# dwm1000v2.net
KiCad netlist of a schematic drawn in EAGLE
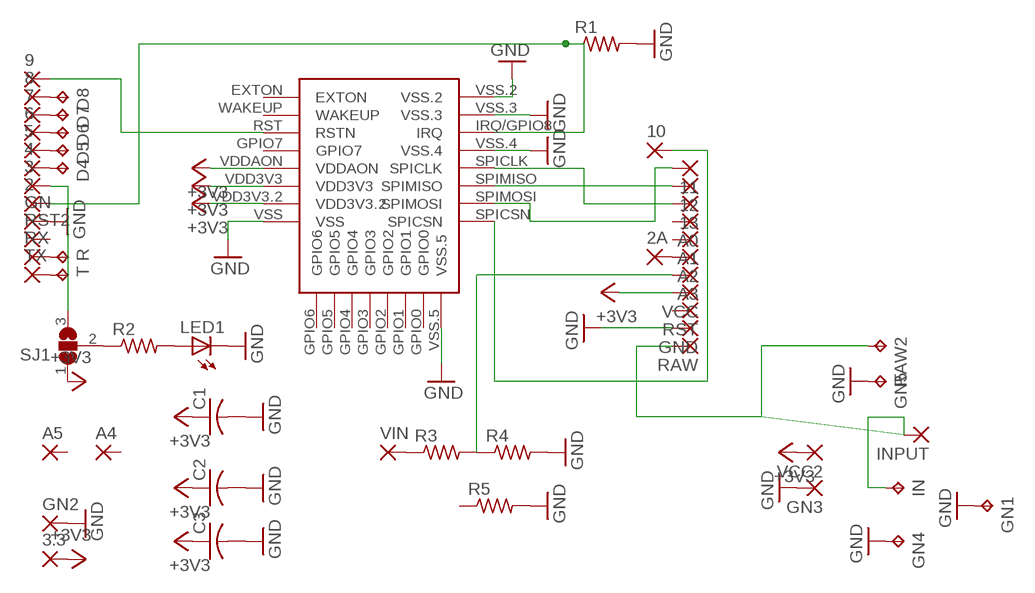
[diagram p0: schematic, sheet 1]

(export (version "E")
  (design (tool "Eeschema 10.0.6"))
  (components
    (comp (ref "2")
      (value "SMD2")
      (footprint "eagle-import:SMD1,27-2,54")
      (libsource (lib "eagle-import") (part "SMD2"))
    )
    (comp (ref "2A")
      (value "SMD2")
      (footprint "eagle-import:SMD1,27-2,54")
      (libsource (lib "eagle-import") (part "SMD2"))
    )
    (comp (ref "3")
      (value "SMD2")
      (footprint "eagle-import:SMD1,27-2,54")
      (libsource (lib "eagle-import") (part "SMD2"))
    )
    (comp (ref "3.3")
      (value "SMD2")
      (footprint "eagle-import:SMD1,27-2,54")
      (libsource (lib "eagle-import") (part "SMD2"))
    )
    (comp (ref "4")
      (value "SMD2")
      (footprint "eagle-import:SMD1,27-2,54")
      (libsource (lib "eagle-import") (part "SMD2"))
    )
    (comp (ref "5")
      (value "SMD2")
      (footprint "eagle-import:SMD1,27-2,54")
      (libsource (lib "eagle-import") (part "SMD2"))
    )
    (comp (ref "6")
      (value "SMD2")
      (footprint "eagle-import:SMD1,27-2,54")
      (libsource (lib "eagle-import") (part "SMD2"))
    )
    (comp (ref "7")
      (value "SMD2")
      (footprint "eagle-import:SMD1,27-2,54")
      (libsource (lib "eagle-import") (part "SMD2"))
    )
    (comp (ref "8")
      (value "SMD2")
      (footprint "eagle-import:SMD1,27-2,54")
      (libsource (lib "eagle-import") (part "SMD2"))
    )
    (comp (ref "9")
      (value "SMD2")
      (footprint "eagle-import:SMD1,27-2,54")
      (libsource (lib "eagle-import") (part "SMD2"))
    )
    (comp (ref "10")
      (value "SMD2")
      (footprint "eagle-import:SMD1,27-2,54")
      (libsource (lib "eagle-import") (part "SMD2"))
    )
    (comp (ref "11")
      (value "SMD2")
      (footprint "eagle-import:SMD1,27-2,54")
      (libsource (lib "eagle-import") (part "SMD2"))
    )
    (comp (ref "12")
      (value "SMD2")
      (footprint "eagle-import:SMD1,27-2,54")
      (libsource (lib "eagle-import") (part "SMD2"))
    )
    (comp (ref "13")
      (value "SMD2")
      (footprint "eagle-import:SMD1,27-2,54")
      (libsource (lib "eagle-import") (part "SMD2"))
    )
    (comp (ref "A0")
      (value "SMD2")
      (footprint "eagle-import:SMD1,27-2,54")
      (libsource (lib "eagle-import") (part "SMD2"))
    )
    (comp (ref "A1")
      (value "SMD2")
      (footprint "eagle-import:SMD1,27-2,54")
      (libsource (lib "eagle-import") (part "SMD2"))
    )
    (comp (ref "A2")
      (value "SMD2")
      (footprint "eagle-import:SMD1,27-2,54")
      (libsource (lib "eagle-import") (part "SMD2"))
    )
    (comp (ref "A3")
      (value "SMD2")
      (footprint "eagle-import:SMD1,27-2,54")
      (libsource (lib "eagle-import") (part "SMD2"))
    )
    (comp (ref "A4")
      (value "1,6/0,8")
      (footprint "eagle-import:1,6_0,8")
      (libsource (lib "eagle-import") (part "1,6/0,8"))
    )
    (comp (ref "A5")
      (value "1,6/0,8")
      (footprint "eagle-import:1,6_0,8")
      (libsource (lib "eagle-import") (part "1,6/0,8"))
    )
    (comp (ref "C1")
      (value "C-USC0805")
      (footprint "eagle-import:C0805")
      (libsource (lib "eagle-import") (part "C-USC0805"))
    )
    (comp (ref "C2")
      (value "C-USC0805")
      (footprint "eagle-import:C0805")
      (libsource (lib "eagle-import") (part "C-USC0805"))
    )
    (comp (ref "C3")
      (value "C-USC0805")
      (footprint "eagle-import:C0805")
      (libsource (lib "eagle-import") (part "C-USC0805"))
    )
    (comp (ref "D4")
      (value "TPTP12SQ")
      (footprint "eagle-import:TP12SQ")
      (libsource (lib "eagle-import") (part "TPTP12SQ"))
    )
    (comp (ref "D5")
      (value "TPTP12SQ")
      (footprint "eagle-import:TP12SQ")
      (libsource (lib "eagle-import") (part "TPTP12SQ"))
    )
    (comp (ref "D6")
      (value "TPTP12SQ")
      (footprint "eagle-import:TP12SQ")
      (libsource (lib "eagle-import") (part "TPTP12SQ"))
    )
    (comp (ref "D7")
      (value "TPTP12SQ")
      (footprint "eagle-import:TP12SQ")
      (libsource (lib "eagle-import") (part "TPTP12SQ"))
    )
    (comp (ref "D8")
      (value "TPTP12SQ")
      (footprint "eagle-import:TP12SQ")
      (libsource (lib "eagle-import") (part "TPTP12SQ"))
    )
    (comp (ref "GN")
      (value "SMD2")
      (footprint "eagle-import:SMD1,27-2,54")
      (libsource (lib "eagle-import") (part "SMD2"))
    )
    (comp (ref "GN1")
      (value "TPTP13SQ")
      (footprint "eagle-import:TP13SQ")
      (libsource (lib "eagle-import") (part "TPTP13SQ"))
    )
    (comp (ref "GN2")
      (value "SMD2")
      (footprint "eagle-import:SMD1,27-2,54")
      (libsource (lib "eagle-import") (part "SMD2"))
    )
    (comp (ref "GN3")
      (value "SMD2")
      (footprint "eagle-import:SMD1,27-2,54")
      (libsource (lib "eagle-import") (part "SMD2"))
    )
    (comp (ref "GN4")
      (value "TPTP13SQ")
      (footprint "eagle-import:TP13SQ")
      (libsource (lib "eagle-import") (part "TPTP13SQ"))
    )
    (comp (ref "GN5")
      (value "TPTP13SQ")
      (footprint "eagle-import:TP13SQ")
      (libsource (lib "eagle-import") (part "TPTP13SQ"))
    )
    (comp (ref "GND")
      (value "SMD2")
      (footprint "eagle-import:SMD1,27-2,54")
      (libsource (lib "eagle-import") (part "SMD2"))
    )
    (comp (ref "IN")
      (value "TPTP13SQ")
      (footprint "eagle-import:TP13SQ")
      (libsource (lib "eagle-import") (part "TPTP13SQ"))
    )
    (comp (ref "INPUT")
      (value "SMD2")
      (footprint "eagle-import:SMD1,27-2,54")
      (libsource (lib "eagle-import") (part "SMD2"))
    )
    (comp (ref "LED1")
      (value "LEDCHIPLED_0805")
      (footprint "eagle-import:CHIPLED_0805")
      (libsource (lib "eagle-import") (part "LEDCHIPLED_0805"))
    )
    (comp (ref "R")
      (value "TPTP12SQ")
      (footprint "eagle-import:TP12SQ")
      (libsource (lib "eagle-import") (part "TPTP12SQ"))
    )
    (comp (ref "R1")
      (value "R-US_R0603")
      (footprint "eagle-import:R0603")
      (libsource (lib "eagle-import") (part "R-US_R0603"))
    )
    (comp (ref "R2")
      (value "R-US_M0805")
      (footprint "eagle-import:M0805")
      (libsource (lib "eagle-import") (part "R-US_M0805"))
    )
    (comp (ref "R3")
      (value "R-US_R0805")
      (footprint "eagle-import:R0805")
      (libsource (lib "eagle-import") (part "R-US_R0805"))
    )
    (comp (ref "R4")
      (value "R-US_R0805")
      (footprint "eagle-import:R0805")
      (libsource (lib "eagle-import") (part "R-US_R0805"))
    )
    (comp (ref "R5")
      (value "R-US_R0805")
      (footprint "eagle-import:R0805")
      (libsource (lib "eagle-import") (part "R-US_R0805"))
    )
    (comp (ref "RAW")
      (value "SMD2")
      (footprint "eagle-import:SMD1,27-2,54")
      (libsource (lib "eagle-import") (part "SMD2"))
    )
    (comp (ref "RAW2")
      (value "TPTP13SQ")
      (footprint "eagle-import:TP13SQ")
      (libsource (lib "eagle-import") (part "TPTP13SQ"))
    )
    (comp (ref "RST")
      (value "SMD2")
      (footprint "eagle-import:SMD1,27-2,54")
      (libsource (lib "eagle-import") (part "SMD2"))
    )
    (comp (ref "RST2")
      (value "SMD2")
      (footprint "eagle-import:SMD1,27-2,54")
      (libsource (lib "eagle-import") (part "SMD2"))
    )
    (comp (ref "RX")
      (value "SMD2")
      (footprint "eagle-import:SMD1,27-2,54")
      (libsource (lib "eagle-import") (part "SMD2"))
    )
    (comp (ref "SJ1")
      (value "SJ2W")
      (footprint "eagle-import:SJ_2")
      (libsource (lib "eagle-import") (part "SJ2W"))
    )
    (comp (ref "T")
      (value "TPTP12SQ")
      (footprint "eagle-import:TP12SQ")
      (libsource (lib "eagle-import") (part "TPTP12SQ"))
    )
    (comp (ref "TX")
      (value "SMD2")
      (footprint "eagle-import:SMD1,27-2,54")
      (libsource (lib "eagle-import") (part "SMD2"))
    )
    (comp (ref "U$1")
      (value "DWM1000")
      (footprint "eagle-import:DWM1000")
      (libsource (lib "eagle-import") (part "DWM1000"))
    )
    (comp (ref "VCC")
      (value "SMD2")
      (footprint "eagle-import:SMD1,27-2,54")
      (libsource (lib "eagle-import") (part "SMD2"))
    )
    (comp (ref "VCC2")
      (value "SMD2")
      (footprint "eagle-import:SMD1,27-2,54")
      (libsource (lib "eagle-import") (part "SMD2"))
    )
    (comp (ref "VIN")
      (value "SMD2")
      (footprint "eagle-import:SMD1,27-2,54")
      (libsource (lib "eagle-import") (part "SMD2"))
    )
  )
  (nets
    (net (code "1") (name "+3V3") (class "Default")
      (node (ref "3.3") (pin "1") (pinfunction "P_1") (pintype "passive"))
      (node (ref "C1") (pin "1") (pinfunction "1_1") (pintype "passive"))
      (node (ref "C2") (pin "1") (pinfunction "1_1") (pintype "passive"))
      (node (ref "C3") (pin "1") (pinfunction "1_1") (pintype "passive"))
      (node (ref "SJ1") (pin "1") (pinfunction "1_1") (pintype "passive"))
      (node (ref "U$1") (pin "VDD3V3") (pinfunction "VDD3V3_VDD3V3") (pintype "bidirectional"))
      (node (ref "U$1") (pin "VDD3V3.2") (pinfunction "VDD3V3.2_VDD3V3.2") (pintype "bidirectional"))
      (node (ref "U$1") (pin "VDDAON") (pinfunction "VDDAON_VDDAON") (pintype "bidirectional"))
      (node (ref "VCC") (pin "1") (pinfunction "P_1") (pintype "passive"))
      (node (ref "VCC2") (pin "1") (pinfunction "P_1") (pintype "passive"))
    )
    (net (code "2") (name "GND") (class "Default")
      (node (ref "C1") (pin "2") (pinfunction "2_2") (pintype "passive"))
      (node (ref "C2") (pin "2") (pinfunction "2_2") (pintype "passive"))
      (node (ref "C3") (pin "2") (pinfunction "2_2") (pintype "passive"))
      (node (ref "GN") (pin "1") (pinfunction "P_1") (pintype "passive"))
      (node (ref "GN1") (pin "TP") (pinfunction "TP_TP") (pintype "input"))
      (node (ref "GN2") (pin "1") (pinfunction "P_1") (pintype "passive"))
      (node (ref "GN3") (pin "1") (pinfunction "P_1") (pintype "passive"))
      (node (ref "GN4") (pin "TP") (pinfunction "TP_TP") (pintype "input"))
      (node (ref "GN5") (pin "TP") (pinfunction "TP_TP") (pintype "input"))
      (node (ref "GND") (pin "1") (pinfunction "P_1") (pintype "passive"))
      (node (ref "LED1") (pin "C") (pinfunction "C_C") (pintype "passive"))
      (node (ref "R1") (pin "2") (pinfunction "2_2") (pintype "passive"))
      (node (ref "R4") (pin "2") (pinfunction "2_2") (pintype "passive"))
      (node (ref "R5") (pin "2") (pinfunction "2_2") (pintype "passive"))
      (node (ref "U$1") (pin "VSS") (pinfunction "VSS_VSS") (pintype "bidirectional"))
      (node (ref "U$1") (pin "VSS.2") (pinfunction "VSS.2_VSS.2") (pintype "bidirectional"))
      (node (ref "U$1") (pin "VSS.3") (pinfunction "VSS.3_VSS.3") (pintype "bidirectional"))
      (node (ref "U$1") (pin "VSS.4") (pinfunction "VSS.4_VSS.4") (pintype "bidirectional"))
      (node (ref "U$1") (pin "VSS.5") (pinfunction "VSS.5_VSS.5") (pintype "bidirectional"))
    )
    (net (code "3") (name "Net-(2-P)") (class "Default")
      (node (ref "2") (pin "1") (pinfunction "P_1") (pintype "passive"))
      (node (ref "R1") (pin "1") (pinfunction "1_1") (pintype "passive"))
      (node (ref "U$1") (pin "IRQ/GPIO8") (pinfunction "IRQ_IRQ/GPIO8") (pintype "bidirectional"))
    )
    (net (code "4") (name "Net-(2A-P)") (class "Default")
      (node (ref "2A") (pin "1") (pinfunction "P_1") (pintype "passive"))
      (node (ref "A2") (pin "1") (pinfunction "P_1") (pintype "passive"))
    )
    (net (code "5") (name "Net-(3-P)") (class "Default")
      (node (ref "3") (pin "1") (pinfunction "P_1") (pintype "passive"))
      (node (ref "SJ1") (pin "3") (pinfunction "3_3") (pintype "passive"))
    )
    (net (code "6") (name "Net-(4-P)") (class "Default")
      (node (ref "4") (pin "1") (pinfunction "P_1") (pintype "passive"))
      (node (ref "D4") (pin "TP") (pinfunction "TP_TP") (pintype "input"))
    )
    (net (code "7") (name "Net-(5-P)") (class "Default")
      (node (ref "5") (pin "1") (pinfunction "P_1") (pintype "passive"))
      (node (ref "D5") (pin "TP") (pinfunction "TP_TP") (pintype "input"))
    )
    (net (code "8") (name "Net-(6-P)") (class "Default")
      (node (ref "6") (pin "1") (pinfunction "P_1") (pintype "passive"))
      (node (ref "D6") (pin "TP") (pinfunction "TP_TP") (pintype "input"))
    )
    (net (code "9") (name "Net-(7-P)") (class "Default")
      (node (ref "7") (pin "1") (pinfunction "P_1") (pintype "passive"))
      (node (ref "D7") (pin "TP") (pinfunction "TP_TP") (pintype "input"))
    )
    (net (code "10") (name "Net-(8-P)") (class "Default")
      (node (ref "8") (pin "1") (pinfunction "P_1") (pintype "passive"))
      (node (ref "D8") (pin "TP") (pinfunction "TP_TP") (pintype "input"))
    )
    (net (code "11") (name "Net-(9-P)") (class "Default")
      (node (ref "9") (pin "1") (pinfunction "P_1") (pintype "passive"))
      (node (ref "U$1") (pin "RST") (pinfunction "RSTN_RST") (pintype "bidirectional"))
    )
    (net (code "12") (name "Net-(10-P)") (class "Default")
      (node (ref "10") (pin "1") (pinfunction "P_1") (pintype "passive"))
      (node (ref "U$1") (pin "SPICSN") (pinfunction "SPICSN_SPICSN") (pintype "bidirectional"))
    )
    (net (code "13") (name "Net-(11-P)") (class "Default")
      (node (ref "11") (pin "1") (pinfunction "P_1") (pintype "passive"))
      (node (ref "U$1") (pin "SPIMOSI") (pinfunction "SPIMOSI_SPIMOSI") (pintype "bidirectional"))
    )
    (net (code "14") (name "Net-(12-P)") (class "Default")
      (node (ref "12") (pin "1") (pinfunction "P_1") (pintype "passive"))
      (node (ref "U$1") (pin "SPIMISO") (pinfunction "SPIMISO_SPIMISO") (pintype "bidirectional"))
    )
    (net (code "15") (name "Net-(13-P)") (class "Default")
      (node (ref "13") (pin "1") (pinfunction "P_1") (pintype "passive"))
      (node (ref "U$1") (pin "SPICLK") (pinfunction "SPICLK_SPICLK") (pintype "bidirectional"))
    )
    (net (code "16") (name "Net-(A3-P)") (class "Default")
      (node (ref "A3") (pin "1") (pinfunction "P_1") (pintype "passive"))
      (node (ref "R3") (pin "2") (pinfunction "2_2") (pintype "passive"))
      (node (ref "R4") (pin "1") (pinfunction "1_1") (pintype "passive"))
    )
    (net (code "17") (name "Net-(INPUT-P)") (class "Default")
      (node (ref "IN") (pin "TP") (pinfunction "TP_TP") (pintype "input"))
      (node (ref "INPUT") (pin "1") (pinfunction "P_1") (pintype "passive"))
      (node (ref "RAW") (pin "1") (pinfunction "P_1") (pintype "passive"))
      (node (ref "RAW2") (pin "TP") (pinfunction "TP_TP") (pintype "input"))
    )
    (net (code "18") (name "Net-(LED1-PadA)") (class "Default")
      (node (ref "LED1") (pin "A") (pinfunction "A_A") (pintype "passive"))
      (node (ref "R2") (pin "2") (pinfunction "2_2") (pintype "passive"))
    )
    (net (code "19") (name "Net-(R2-Pad1)") (class "Default")
      (node (ref "R2") (pin "1") (pinfunction "1_1") (pintype "passive"))
      (node (ref "SJ1") (pin "2") (pinfunction "2_2") (pintype "passive"))
    )
    (net (code "20") (name "Net-(RX-P)") (class "Default")
      (node (ref "R") (pin "TP") (pinfunction "TP_TP") (pintype "input"))
      (node (ref "RX") (pin "1") (pinfunction "P_1") (pintype "passive"))
    )
    (net (code "21") (name "Net-(TX-P)") (class "Default")
      (node (ref "T") (pin "TP") (pinfunction "TP_TP") (pintype "input"))
      (node (ref "TX") (pin "1") (pinfunction "P_1") (pintype "passive"))
    )
    (net (code "22") (name "Net-(VIN-P)") (class "Default")
      (node (ref "R3") (pin "1") (pinfunction "1_1") (pintype "passive"))
      (node (ref "VIN") (pin "1") (pinfunction "P_1") (pintype "passive"))
    )
    (net (code "23") (name "unconnected-(A0-P-Pad1)") (class "Default")
      (node (ref "A0") (pin "1") (pinfunction "P_1") (pintype "passive"))
    )
    (net (code "24") (name "unconnected-(A1-P-Pad1)") (class "Default")
      (node (ref "A1") (pin "1") (pinfunction "P_1") (pintype "passive"))
    )
    (net (code "25") (name "unconnected-(A4-P-Pad1)") (class "Default")
      (node (ref "A4") (pin "1") (pinfunction "P_1") (pintype "passive"))
    )
    (net (code "26") (name "unconnected-(A5-P-Pad1)") (class "Default")
      (node (ref "A5") (pin "1") (pinfunction "P_1") (pintype "passive"))
    )
    (net (code "27") (name "unconnected-(R5-Pad1)") (class "Default")
      (node (ref "R5") (pin "1") (pinfunction "1_1") (pintype "passive"))
    )
    (net (code "28") (name "unconnected-(RST-P-Pad1)") (class "Default")
      (node (ref "RST") (pin "1") (pinfunction "P_1") (pintype "passive"))
    )
    (net (code "29") (name "unconnected-(RST2-P-Pad1)") (class "Default")
      (node (ref "RST2") (pin "1") (pinfunction "P_1") (pintype "passive"))
    )
    (net (code "30") (name "unconnected-(U$1-PadEXTON)") (class "Default")
      (node (ref "U$1") (pin "EXTON") (pinfunction "EXTON_EXTON") (pintype "bidirectional"))
    )
    (net (code "31") (name "unconnected-(U$1-PadGPIO0)") (class "Default")
      (node (ref "U$1") (pin "GPIO0") (pinfunction "GPIO0_GPIO0") (pintype "bidirectional"))
    )
    (net (code "32") (name "unconnected-(U$1-PadGPIO1)") (class "Default")
      (node (ref "U$1") (pin "GPIO1") (pinfunction "GPIO1_GPIO1") (pintype "bidirectional"))
    )
    (net (code "33") (name "unconnected-(U$1-PadGPIO2)") (class "Default")
      (node (ref "U$1") (pin "GPIO2") (pinfunction "GPIO2_GPIO2") (pintype "bidirectional"))
    )
    (net (code "34") (name "unconnected-(U$1-PadGPIO3)") (class "Default")
      (node (ref "U$1") (pin "GPIO3") (pinfunction "GPIO3_GPIO3") (pintype "bidirectional"))
    )
    (net (code "35") (name "unconnected-(U$1-PadGPIO4)") (class "Default")
      (node (ref "U$1") (pin "GPIO4") (pinfunction "GPIO4_GPIO4") (pintype "bidirectional"))
    )
    (net (code "36") (name "unconnected-(U$1-PadGPIO5)") (class "Default")
      (node (ref "U$1") (pin "GPIO5") (pinfunction "GPIO5_GPIO5") (pintype "bidirectional"))
    )
    (net (code "37") (name "unconnected-(U$1-PadGPIO6)") (class "Default")
      (node (ref "U$1") (pin "GPIO6") (pinfunction "GPIO6_GPIO6") (pintype "bidirectional"))
    )
    (net (code "38") (name "unconnected-(U$1-PadGPIO7)") (class "Default")
      (node (ref "U$1") (pin "GPIO7") (pinfunction "GPIO7_GPIO7") (pintype "bidirectional"))
    )
    (net (code "39") (name "unconnected-(U$1-PadWAKEUP)") (class "Default")
      (node (ref "U$1") (pin "WAKEUP") (pinfunction "WAKEUP_WAKEUP") (pintype "bidirectional"))
    )
  )
)
